# PiCycle_PCB.net
KiCad netlist of a schematic drawn in EAGLE
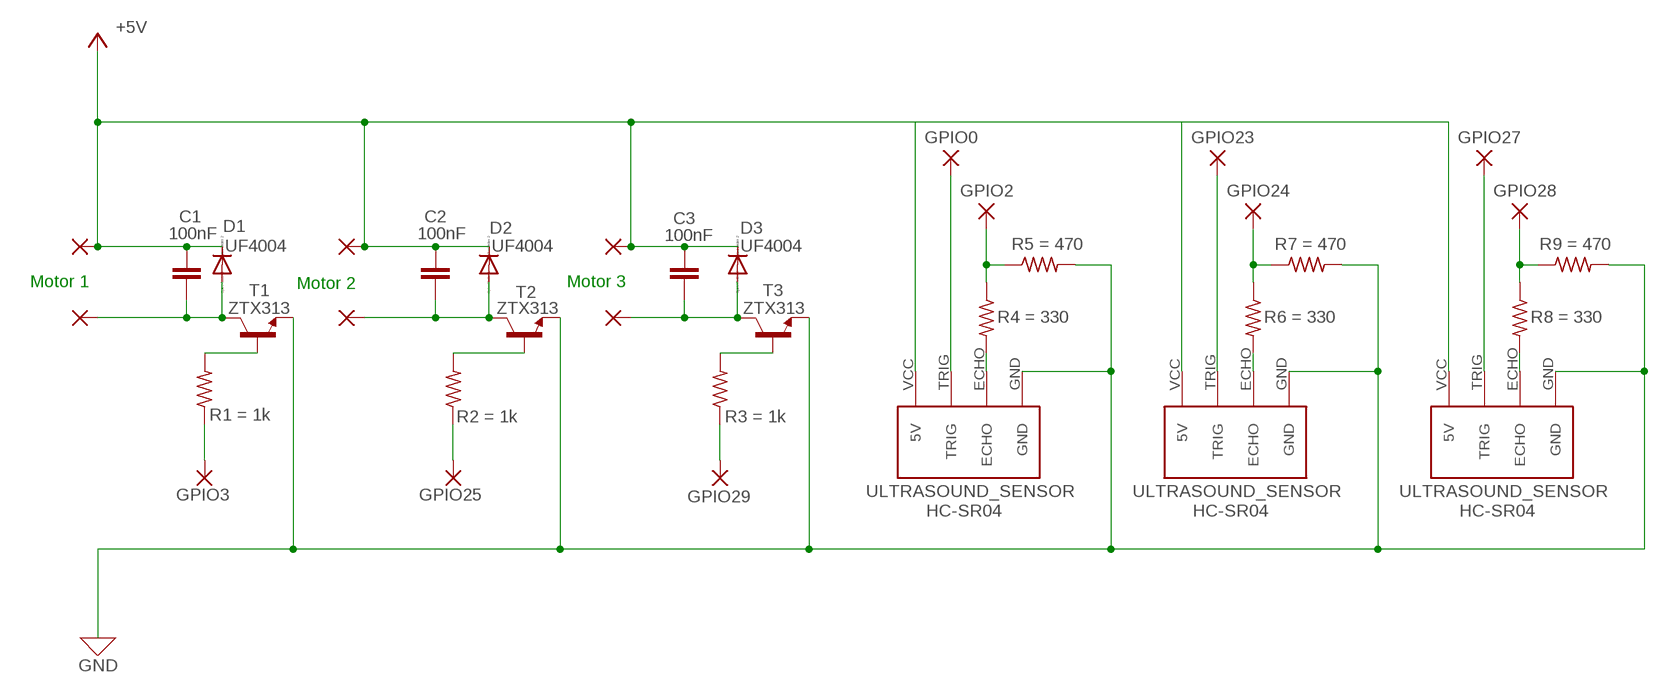
[diagram p0: schematic, sheet 1]

(export (version "E")
  (design (tool "Eeschema 10.0.6"))
  (components
    (comp (ref "C1")
      (value "C15/6")
      (footprint "eagle-import:C15B6")
      (fields (field (name "CAPPYU") "100nF"))
      (libsource (lib "eagle-import") (part "C15/6"))
    )
    (comp (ref "C2")
      (value "C15/6")
      (footprint "eagle-import:C15B6")
      (fields (field (name "CAPPY") "100nF"))
      (libsource (lib "eagle-import") (part "C15/6"))
    )
    (comp (ref "C3")
      (value "C15/6")
      (footprint "eagle-import:C15B6")
      (fields (field (name "CAPPY") "100nF"))
      (libsource (lib "eagle-import") (part "C15/6"))
    )
    (comp (ref "D1")
      (value "BA243A")
      (footprint "eagle-import:DO35-10")
      (libsource (lib "eagle-import") (part "BA243A"))
    )
    (comp (ref "D2")
      (value "BA243A")
      (footprint "eagle-import:DO35-10")
      (libsource (lib "eagle-import") (part "BA243A"))
    )
    (comp (ref "D3")
      (value "BA243A")
      (footprint "eagle-import:DO35-10")
      (libsource (lib "eagle-import") (part "BA243A"))
    )
    (comp (ref "J_ULTRASONIC_1")
      (value "HC-SR04")
      (footprint "eagle-import:HC-SR04_FOOTPRINT")
      (libsource (lib "eagle-import") (part "HC-SR04"))
    )
    (comp (ref "J_ULTRASONIC_2")
      (value "HC-SR04")
      (footprint "eagle-import:HC-SR04_FOOTPRINT")
      (libsource (lib "eagle-import") (part "HC-SR04"))
    )
    (comp (ref "J_ULTRASONIC_3")
      (value "HC-SR04")
      (footprint "eagle-import:HC-SR04_FOOTPRINT")
      (libsource (lib "eagle-import") (part "HC-SR04"))
    )
    (comp (ref "PAD1")
      (value "3,81/1,4")
      (footprint "eagle-import:3,81_1,4")
      (libsource (lib "eagle-import") (part "3,81/1,4"))
    )
    (comp (ref "PAD2")
      (value "3,81/1,4")
      (footprint "eagle-import:3,81_1,4")
      (libsource (lib "eagle-import") (part "3,81/1,4"))
    )
    (comp (ref "PAD3")
      (value "3,81/1,4")
      (footprint "eagle-import:3,81_1,4")
      (libsource (lib "eagle-import") (part "3,81/1,4"))
    )
    (comp (ref "PAD4")
      (value "3,81/1,4")
      (footprint "eagle-import:3,81_1,4")
      (libsource (lib "eagle-import") (part "3,81/1,4"))
    )
    (comp (ref "PAD5")
      (value "3,81/1,4")
      (footprint "eagle-import:3,81_1,4")
      (libsource (lib "eagle-import") (part "3,81/1,4"))
    )
    (comp (ref "PAD6")
      (value "3,81/1,4")
      (footprint "eagle-import:3,81_1,4")
      (libsource (lib "eagle-import") (part "3,81/1,4"))
    )
    (comp (ref "PAD7")
      (value "3,81/1,4")
      (footprint "eagle-import:3,81_1,4")
      (libsource (lib "eagle-import") (part "3,81/1,4"))
    )
    (comp (ref "PAD8")
      (value "3,81/1,4")
      (footprint "eagle-import:3,81_1,4")
      (libsource (lib "eagle-import") (part "3,81/1,4"))
    )
    (comp (ref "PAD9")
      (value "3,81/1,4")
      (footprint "eagle-import:3,81_1,4")
      (libsource (lib "eagle-import") (part "3,81/1,4"))
    )
    (comp (ref "PAD10")
      (value "3,81/1,4")
      (footprint "eagle-import:3,81_1,4")
      (libsource (lib "eagle-import") (part "3,81/1,4"))
    )
    (comp (ref "PAD11")
      (value "3,81/1,4")
      (footprint "eagle-import:3,81_1,4")
      (libsource (lib "eagle-import") (part "3,81/1,4"))
    )
    (comp (ref "PAD12")
      (value "3,81/1,4")
      (footprint "eagle-import:3,81_1,4")
      (libsource (lib "eagle-import") (part "3,81/1,4"))
    )
    (comp (ref "PAD13")
      (value "3,81/1,4")
      (footprint "eagle-import:3,81_1,4")
      (libsource (lib "eagle-import") (part "3,81/1,4"))
    )
    (comp (ref "PAD14")
      (value "3,81/1,4")
      (footprint "eagle-import:3,81_1,4")
      (libsource (lib "eagle-import") (part "3,81/1,4"))
    )
    (comp (ref "PAD15")
      (value "3,81/1,4")
      (footprint "eagle-import:3,81_1,4")
      (libsource (lib "eagle-import") (part "3,81/1,4"))
    )
    (comp (ref "R1")
      (value "R-US_0207/15")
      (footprint "eagle-import:0207_15")
      (fields (field (name "R1") "1k") (field (name "SPICEPREFIX") "1k"))
      (libsource (lib "eagle-import") (part "R-US_0207/15"))
    )
    (comp (ref "R2")
      (value "R-US_0207/15")
      (footprint "eagle-import:0207_15")
      (fields (field (name "R2") "1k") (field (name "SPICEPREFIX") "1k"))
      (libsource (lib "eagle-import") (part "R-US_0207/15"))
    )
    (comp (ref "R3")
      (value "R-US_0207/15")
      (footprint "eagle-import:0207_15")
      (fields (field (name "R3") "1k") (field (name "SPICEPREFIX") "1k"))
      (libsource (lib "eagle-import") (part "R-US_0207/15"))
    )
    (comp (ref "R4")
      (value "R-US_0207/15")
      (footprint "eagle-import:0207_15")
      (fields (field (name "R6") "330") (field (name "SPICEPREFIX") "1k"))
      (libsource (lib "eagle-import") (part "R-US_0207/15"))
    )
    (comp (ref "R5")
      (value "R-US_0207/15")
      (footprint "eagle-import:0207_15")
      (fields (field (name "R7") "470") (field (name "SPICEPREFIX") "1k"))
      (libsource (lib "eagle-import") (part "R-US_0207/15"))
    )
    (comp (ref "R6")
      (value "R-US_0207/15")
      (footprint "eagle-import:0207_15")
      (fields (field (name "R8") "330") (field (name "SPICEPREFIX") "1k"))
      (libsource (lib "eagle-import") (part "R-US_0207/15"))
    )
    (comp (ref "R7")
      (value "R-US_0207/15")
      (footprint "eagle-import:0207_15")
      (fields (field (name "R9") "470") (field (name "SPICEPREFIX") "1k"))
      (libsource (lib "eagle-import") (part "R-US_0207/15"))
    )
    (comp (ref "R8")
      (value "R-US_0207/15")
      (footprint "eagle-import:0207_15")
      (fields (field (name "R4") "330") (field (name "SPICEPREFIX") "1k"))
      (libsource (lib "eagle-import") (part "R-US_0207/15"))
    )
    (comp (ref "R9")
      (value "R-US_0207/15")
      (footprint "eagle-import:0207_15")
      (fields (field (name "R5") "470") (field (name "SPICEPREFIX") "1k"))
      (libsource (lib "eagle-import") (part "R-US_0207/15"))
    )
    (comp (ref "T1")
      (value "2N706")
      (footprint "eagle-import:TO18")
      (libsource (lib "eagle-import") (part "2N706"))
    )
    (comp (ref "T2")
      (value "2N706")
      (footprint "eagle-import:TO18")
      (libsource (lib "eagle-import") (part "2N706"))
    )
    (comp (ref "T3")
      (value "2N706")
      (footprint "eagle-import:TO18")
      (libsource (lib "eagle-import") (part "2N706"))
    )
  )
  (nets
    (net (code "1") (name "+5V") (class "Default")
      (node (ref "C1") (pin "1") (pinfunction "1_1") (pintype "passive"))
      (node (ref "C2") (pin "1") (pinfunction "1_1") (pintype "passive"))
      (node (ref "C3") (pin "1") (pinfunction "1_1") (pintype "passive"))
      (node (ref "D1") (pin "C") (pinfunction "C_C") (pintype "passive"))
      (node (ref "D2") (pin "C") (pinfunction "C_C") (pintype "passive"))
      (node (ref "D3") (pin "C") (pinfunction "C_C") (pintype "passive"))
      (node (ref "J_ULTRASONIC_1") (pin "VCC") (pinfunction "5V_VCC") (pintype "bidirectional"))
      (node (ref "PAD5") (pin "1") (pinfunction "P_1") (pintype "passive"))
      (node (ref "PAD6") (pin "1") (pinfunction "P_1") (pintype "passive"))
      (node (ref "PAD9") (pin "1") (pinfunction "P_1") (pintype "passive"))
    )
    (net (code "2") (name "GND") (class "Default")
      (node (ref "J_ULTRASONIC_1") (pin "GND") (pinfunction "GND_GND") (pintype "bidirectional"))
      (node (ref "J_ULTRASONIC_2") (pin "GND") (pinfunction "GND_GND") (pintype "bidirectional"))
      (node (ref "J_ULTRASONIC_3") (pin "GND") (pinfunction "GND_GND") (pintype "bidirectional"))
      (node (ref "R5") (pin "2") (pinfunction "2_2") (pintype "passive"))
      (node (ref "R7") (pin "2") (pinfunction "2_2") (pintype "passive"))
      (node (ref "R9") (pin "2") (pinfunction "2_2") (pintype "passive"))
      (node (ref "T1") (pin "1") (pinfunction "E_1") (pintype "passive"))
      (node (ref "T2") (pin "1") (pinfunction "E_1") (pintype "passive"))
      (node (ref "T3") (pin "1") (pinfunction "E_1") (pintype "passive"))
    )
    (net (code "3") (name "Net-(J_ULTRASONIC_1-PadECHO)") (class "Default")
      (node (ref "J_ULTRASONIC_1") (pin "ECHO") (pinfunction "ECHO_ECHO") (pintype "bidirectional"))
      (node (ref "R8") (pin "2") (pinfunction "2_2") (pintype "passive"))
    )
    (net (code "4") (name "Net-(J_ULTRASONIC_2-PadECHO)") (class "Default")
      (node (ref "J_ULTRASONIC_2") (pin "ECHO") (pinfunction "ECHO_ECHO") (pintype "bidirectional"))
      (node (ref "R4") (pin "2") (pinfunction "2_2") (pintype "passive"))
    )
    (net (code "5") (name "Net-(J_ULTRASONIC_3-PadECHO)") (class "Default")
      (node (ref "J_ULTRASONIC_3") (pin "ECHO") (pinfunction "ECHO_ECHO") (pintype "bidirectional"))
      (node (ref "R6") (pin "2") (pinfunction "2_2") (pintype "passive"))
    )
    (net (code "6") (name "Net-(PAD1-P)") (class "Default")
      (node (ref "PAD1") (pin "1") (pinfunction "P_1") (pintype "passive"))
      (node (ref "R1") (pin "1") (pinfunction "1_1") (pintype "passive"))
    )
    (net (code "7") (name "Net-(PAD2-P)") (class "Default")
      (node (ref "PAD2") (pin "1") (pinfunction "P_1") (pintype "passive"))
      (node (ref "R2") (pin "1") (pinfunction "1_1") (pintype "passive"))
    )
    (net (code "8") (name "Net-(PAD3-P)") (class "Default")
      (node (ref "PAD3") (pin "1") (pinfunction "P_1") (pintype "passive"))
      (node (ref "R3") (pin "1") (pinfunction "1_1") (pintype "passive"))
    )
    (net (code "9") (name "Net-(PAD4-P)") (class "Default")
      (node (ref "C1") (pin "2") (pinfunction "2_2") (pintype "passive"))
      (node (ref "D1") (pin "A") (pinfunction "A_A") (pintype "passive"))
      (node (ref "PAD4") (pin "1") (pinfunction "P_1") (pintype "passive"))
      (node (ref "T1") (pin "3") (pinfunction "C_3") (pintype "passive"))
    )
    (net (code "10") (name "Net-(PAD7-P)") (class "Default")
      (node (ref "C2") (pin "2") (pinfunction "2_2") (pintype "passive"))
      (node (ref "D2") (pin "A") (pinfunction "A_A") (pintype "passive"))
      (node (ref "PAD7") (pin "1") (pinfunction "P_1") (pintype "passive"))
      (node (ref "T2") (pin "3") (pinfunction "C_3") (pintype "passive"))
    )
    (net (code "11") (name "Net-(PAD8-P)") (class "Default")
      (node (ref "C3") (pin "2") (pinfunction "2_2") (pintype "passive"))
      (node (ref "D3") (pin "A") (pinfunction "A_A") (pintype "passive"))
      (node (ref "PAD8") (pin "1") (pinfunction "P_1") (pintype "passive"))
      (node (ref "T3") (pin "3") (pinfunction "C_3") (pintype "passive"))
    )
    (net (code "12") (name "Net-(PAD10-P)") (class "Default")
      (node (ref "J_ULTRASONIC_2") (pin "TRIG") (pinfunction "TRIG_TRIG") (pintype "bidirectional"))
      (node (ref "PAD10") (pin "1") (pinfunction "P_1") (pintype "passive"))
    )
    (net (code "13") (name "Net-(PAD11-P)") (class "Default")
      (node (ref "J_ULTRASONIC_1") (pin "TRIG") (pinfunction "TRIG_TRIG") (pintype "bidirectional"))
      (node (ref "PAD11") (pin "1") (pinfunction "P_1") (pintype "passive"))
    )
    (net (code "14") (name "Net-(PAD12-P)") (class "Default")
      (node (ref "PAD12") (pin "1") (pinfunction "P_1") (pintype "passive"))
      (node (ref "R4") (pin "1") (pinfunction "1_1") (pintype "passive"))
      (node (ref "R5") (pin "1") (pinfunction "1_1") (pintype "passive"))
    )
    (net (code "15") (name "Net-(PAD13-P)") (class "Default")
      (node (ref "J_ULTRASONIC_3") (pin "TRIG") (pinfunction "TRIG_TRIG") (pintype "bidirectional"))
      (node (ref "PAD13") (pin "1") (pinfunction "P_1") (pintype "passive"))
    )
    (net (code "16") (name "Net-(PAD14-P)") (class "Default")
      (node (ref "PAD14") (pin "1") (pinfunction "P_1") (pintype "passive"))
      (node (ref "R6") (pin "1") (pinfunction "1_1") (pintype "passive"))
      (node (ref "R7") (pin "1") (pinfunction "1_1") (pintype "passive"))
    )
    (net (code "17") (name "Net-(PAD15-P)") (class "Default")
      (node (ref "PAD15") (pin "1") (pinfunction "P_1") (pintype "passive"))
      (node (ref "R8") (pin "1") (pinfunction "1_1") (pintype "passive"))
      (node (ref "R9") (pin "1") (pinfunction "1_1") (pintype "passive"))
    )
    (net (code "18") (name "Net-(T1-B)") (class "Default")
      (node (ref "R1") (pin "2") (pinfunction "2_2") (pintype "passive"))
      (node (ref "T1") (pin "2") (pinfunction "B_2") (pintype "passive"))
    )
    (net (code "19") (name "Net-(T2-B)") (class "Default")
      (node (ref "R2") (pin "2") (pinfunction "2_2") (pintype "passive"))
      (node (ref "T2") (pin "2") (pinfunction "B_2") (pintype "passive"))
    )
    (net (code "20") (name "Net-(T3-B)") (class "Default")
      (node (ref "R3") (pin "2") (pinfunction "2_2") (pintype "passive"))
      (node (ref "T3") (pin "2") (pinfunction "B_2") (pintype "passive"))
    )
    (net (code "21") (name "unconnected-(J_ULTRASONIC_2-5V-PadVCC)") (class "Default")
      (node (ref "J_ULTRASONIC_2") (pin "VCC") (pinfunction "5V_VCC") (pintype "bidirectional"))
    )
    (net (code "22") (name "unconnected-(J_ULTRASONIC_3-5V-PadVCC)") (class "Default")
      (node (ref "J_ULTRASONIC_3") (pin "VCC") (pinfunction "5V_VCC") (pintype "bidirectional"))
    )
  )
)
